# New_Project_2025-09-08_15-52-52.net
KiCad netlist of a schematic drawn in EasyEDA Pro
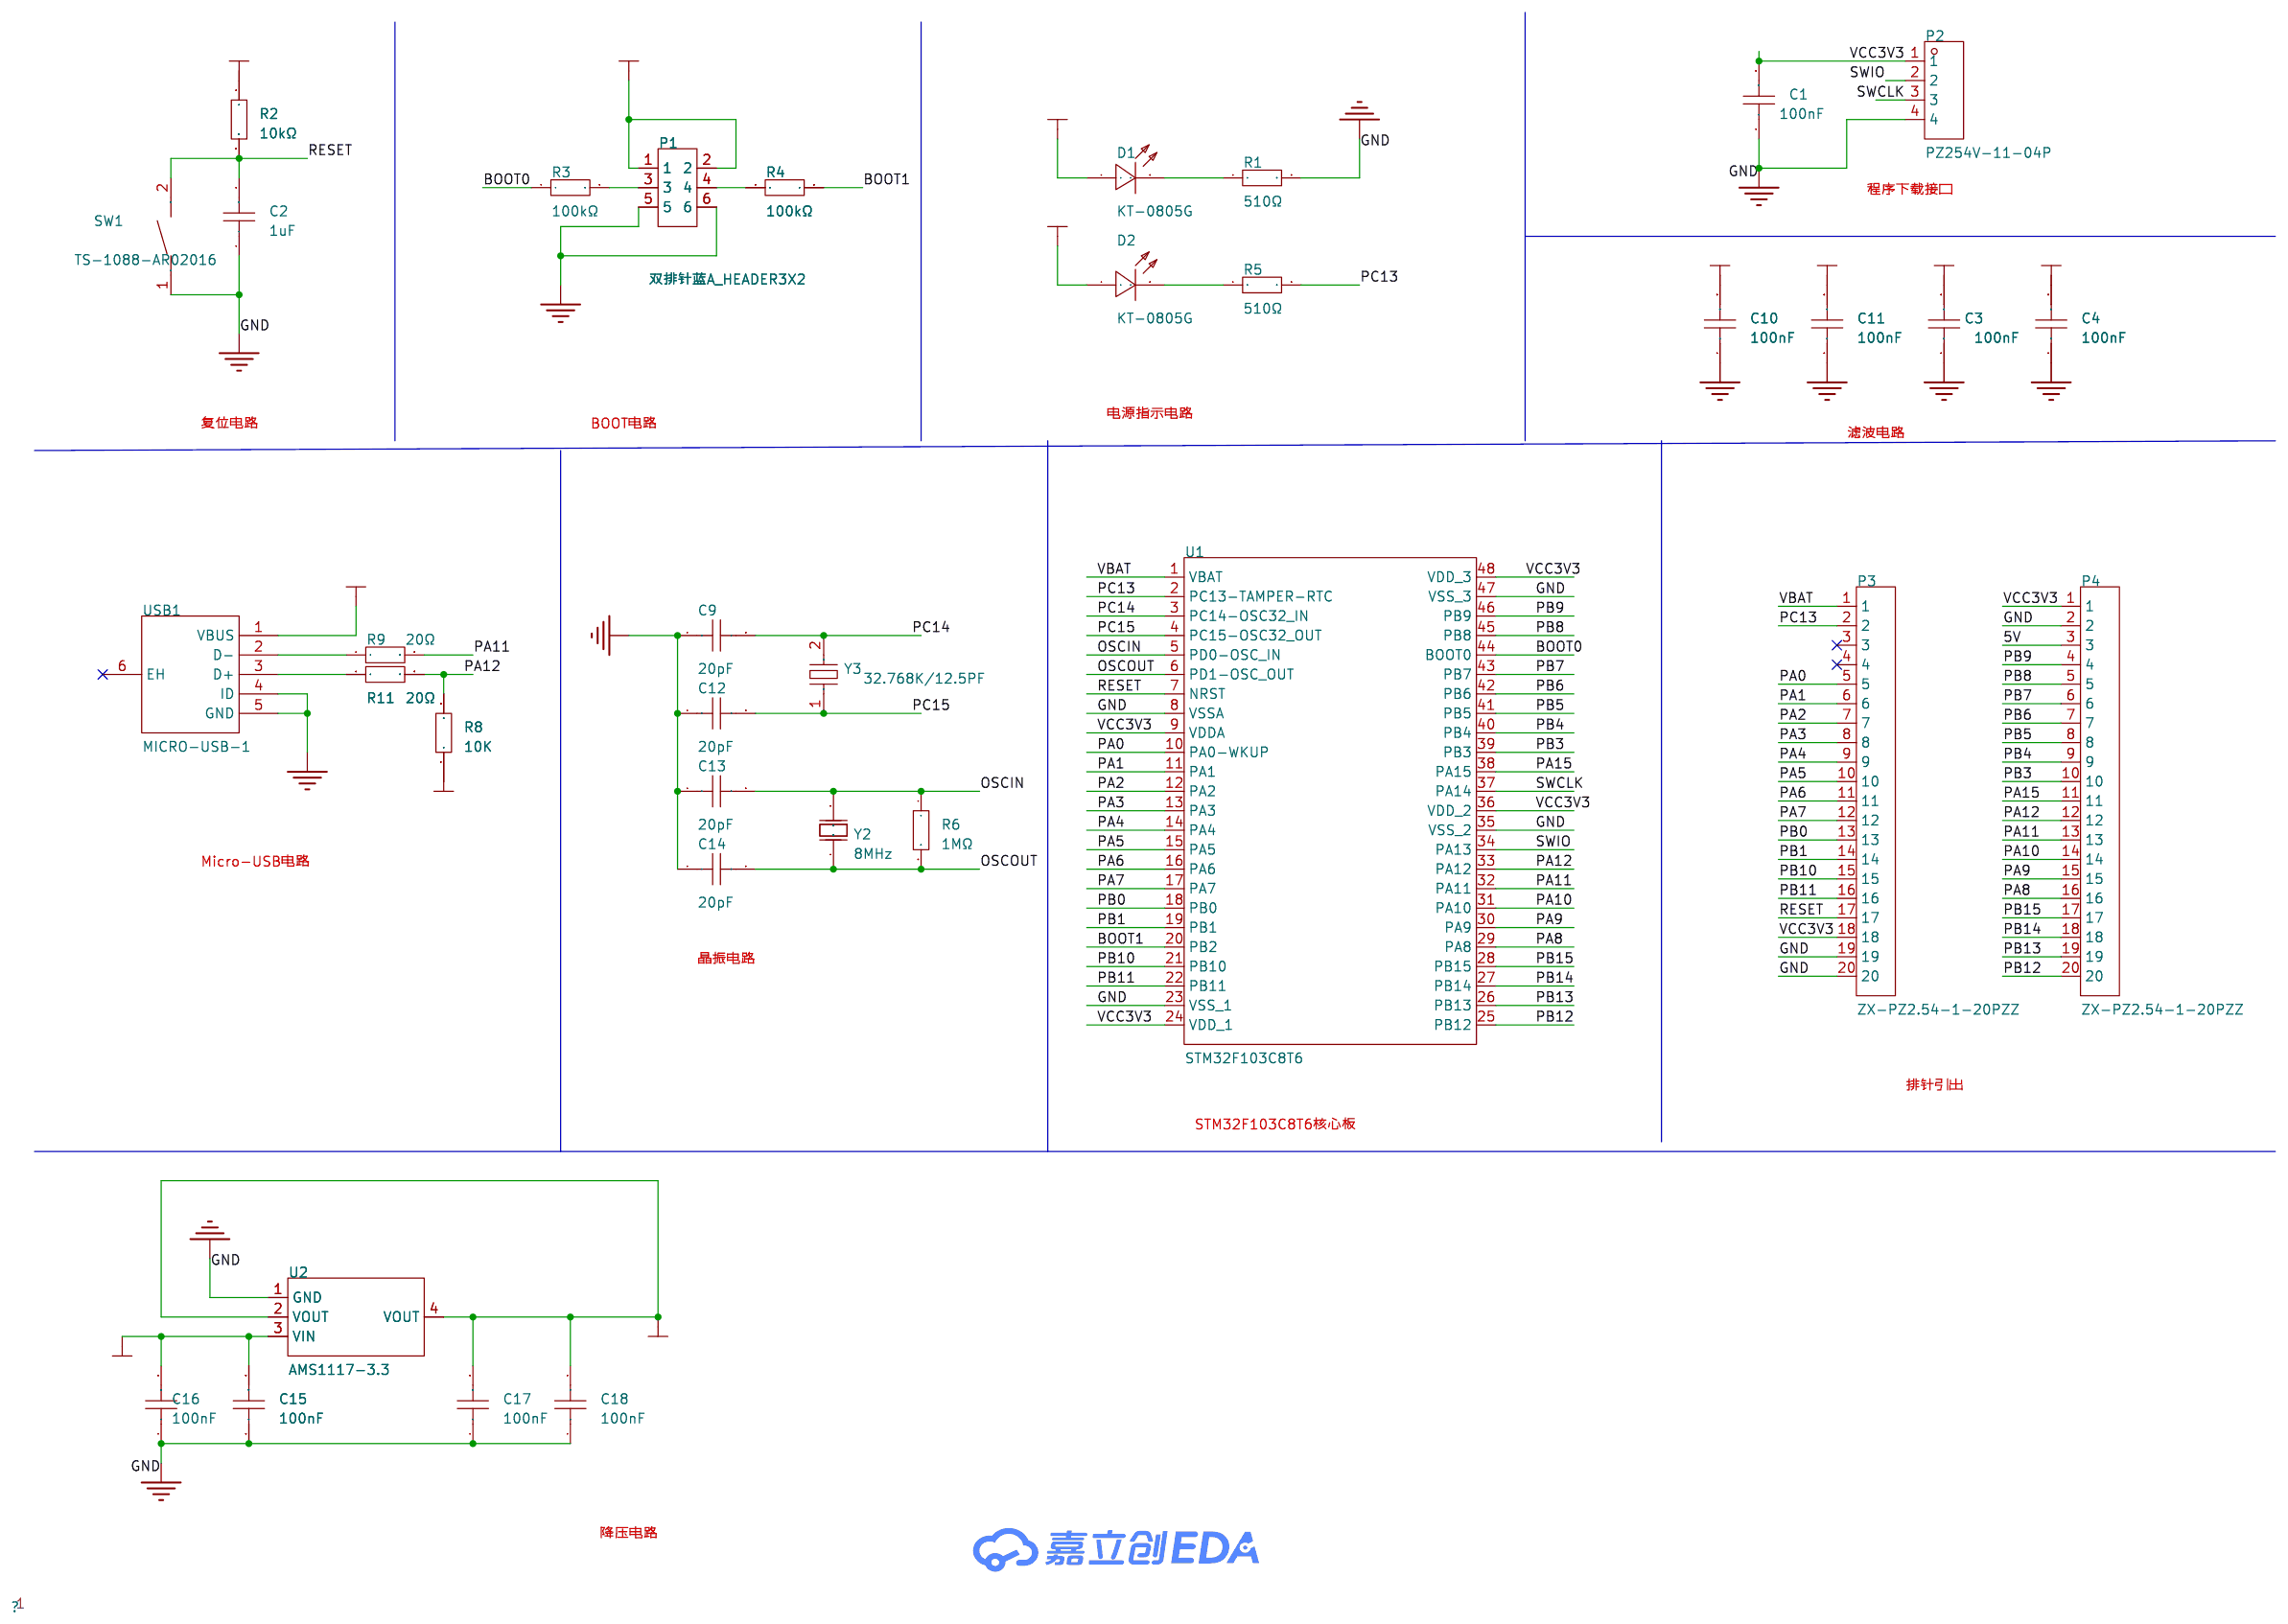
[diagram p0: schematic sheet]

(export (version "E")
  (design (tool "Eeschema 10.0.6"))
  (components
    (comp (ref "C1")
      (value "100nF")
      (footprint "easyedapro:C0603")
      (libsource (lib "easyedapro") (part "Capacitance"))
    )
    (comp (ref "C2")
      (value "1uF")
      (footprint "easyedapro:C0603")
      (libsource (lib "easyedapro") (part "Capacitance"))
    )
    (comp (ref "C3")
      (value "100nF")
      (footprint "easyedapro:C0603")
      (libsource (lib "easyedapro") (part "Capacitance"))
    )
    (comp (ref "C4")
      (value "100nF")
      (footprint "easyedapro:C0603")
      (libsource (lib "easyedapro") (part "Capacitance"))
    )
    (comp (ref "C9")
      (value "20pF")
      (footprint "easyedapro:C0603")
      (libsource (lib "easyedapro") (part "Capacitance"))
    )
    (comp (ref "C10")
      (value "100nF")
      (footprint "easyedapro:C0603")
      (libsource (lib "easyedapro") (part "Capacitance"))
    )
    (comp (ref "C11")
      (value "100nF")
      (footprint "easyedapro:C0603")
      (libsource (lib "easyedapro") (part "Capacitance"))
    )
    (comp (ref "C12")
      (value "20pF")
      (footprint "easyedapro:C0603")
      (libsource (lib "easyedapro") (part "Capacitance"))
    )
    (comp (ref "C13")
      (value "20pF")
      (footprint "easyedapro:C0603")
      (libsource (lib "easyedapro") (part "Capacitance"))
    )
    (comp (ref "C14")
      (value "20pF")
      (footprint "easyedapro:C0603")
      (libsource (lib "easyedapro") (part "Capacitance"))
    )
    (comp (ref "C15")
      (value "100nF")
      (footprint "easyedapro:C0603")
      (libsource (lib "easyedapro") (part "Capacitance"))
    )
    (comp (ref "C16")
      (value "100nF")
      (footprint "easyedapro:C0603")
      (libsource (lib "easyedapro") (part "Capacitance"))
    )
    (comp (ref "C17")
      (value "100nF")
      (footprint "easyedapro:C0603")
      (libsource (lib "easyedapro") (part "Capacitance"))
    )
    (comp (ref "C18")
      (value "100nF")
      (footprint "easyedapro:C0603")
      (libsource (lib "easyedapro") (part "Capacitance"))
    )
    (comp (ref "D1")
      (value "KT-0805G")
      (footprint "easyedapro:LED0805-R-RD")
      (fields (field (name "Manufacturer") "KENTO"))
      (libsource (lib "easyedapro") (part "0805G (Green)"))
    )
    (comp (ref "D2")
      (value "KT-0805G")
      (footprint "easyedapro:LED0805-R-RD")
      (fields (field (name "Manufacturer") "KENTO"))
      (libsource (lib "easyedapro") (part "0805G (Green)"))
    )
    (comp (ref "P1")
      (value "双排针蓝A_HEADER3X2")
      (footprint "easyedapro:HDR-TH_6P-P2.54-V-M-R2-C3-S2.54-1")
      (libsource (lib "easyedapro") (part "双排针蓝A_HEADER3X2"))
    )
    (comp (ref "P2")
      (value "PZ254V-11-04P")
      (footprint "easyedapro:HDR-TH_4P-P2.54-V-M")
      (fields (field (name "Manufacturer") "XFCN(兴飞)"))
      (libsource (lib "easyedapro") (part "PZ254V-11-04P_C2691448"))
    )
    (comp (ref "P3")
      (value "ZX-PZ2.54-1-20PZZ")
      (footprint "easyedapro:HDR-TH_20P-P2.54-V-M")
      (fields (field (name "Manufacturer") "Megastar(兆星)"))
      (libsource (lib "easyedapro") (part "ZX-PZ2.54-1-20PZZ"))
    )
    (comp (ref "P4")
      (value "ZX-PZ2.54-1-20PZZ")
      (footprint "easyedapro:HDR-TH_20P-P2.54-V-M")
      (fields (field (name "Manufacturer") "Megastar(兆星)"))
      (libsource (lib "easyedapro") (part "ZX-PZ2.54-1-20PZZ"))
    )
    (comp (ref "R1") (value "510Ω") (footprint "easyedapro:R0603") (libsource (lib "easyedapro") (part "电阻")))
    (comp (ref "R2") (value "10kΩ") (footprint "easyedapro:R0603") (libsource (lib "easyedapro") (part "电阻")))
    (comp (ref "R3")
      (value "100kΩ")
      (footprint "easyedapro:R0603")
      (libsource (lib "easyedapro") (part "电阻"))
    )
    (comp (ref "R4")
      (value "100kΩ")
      (footprint "easyedapro:R0603")
      (libsource (lib "easyedapro") (part "电阻"))
    )
    (comp (ref "R5") (value "510Ω") (footprint "easyedapro:R0603") (libsource (lib "easyedapro") (part "电阻")))
    (comp (ref "R6") (value "1MΩ") (footprint "easyedapro:R0603") (libsource (lib "easyedapro") (part "电阻")))
    (comp (ref "R8") (value "10K") (footprint "easyedapro:R0603") (libsource (lib "easyedapro") (part "电阻")))
    (comp (ref "R9") (value "20Ω") (footprint "easyedapro:R0603") (libsource (lib "easyedapro") (part "电阻")))
    (comp (ref "R11") (value "20Ω") (footprint "easyedapro:R0603") (libsource (lib "easyedapro") (part "电阻")))
    (comp (ref "SW1")
      (value "TS-1088-AR02016")
      (footprint "easyedapro:SW-SMD_L3.9-W3.0-P4.45")
      (fields (field (name "Manufacturer") "XUNPU(讯普)"))
      (libsource (lib "easyedapro") (part "TS-1088-AR02016"))
    )
    (comp (ref "U1")
      (value "STM32F103C8T6")
      (footprint "easyedapro:LQFP-48_L7.0-W7.0-P0.50-LS9.0-BL")
      (description "CPU内核:ARM-M3;CPU最大主频:72MHz;应用领域:-;")
      (fields (field (name "Manufacturer") "ST(意法半导体)"))
      (libsource (lib "easyedapro") (part "STM32F103C8T6"))
    )
    (comp (ref "U2")
      (value "AMS1117-3.3")
      (footprint "easyedapro:SOT-223-3_L6.5-W3.4-P2.30-LS7.0-BR")
      (description "输出类型:固定;工作电压:16V;输出电压:3.3V;输出电流:1A;电源纹波抑制比(PSRR):72dB@(120Hz);输出极性:正极;")
      (fields (field (name "Manufacturer") "AMS"))
      (libsource (lib "easyedapro") (part "AMS1117-3.3"))
    )
    (comp (ref "USB1")
      (value "MICRO-USB-1")
      (footprint "easyedapro:MICRO-USB-SMD_C9900008946")
      (libsource (lib "easyedapro") (part "MICRO-USB-1"))
    )
    (comp (ref "Y2")
      (value "8MHz")
      (footprint "easyedapro:HC-49U_L10.9-W4.5-P4.88")
      (description "频率:8MHz;常温频差:±30ppm;外接负载电容:-;频率稳定度(全温):±50ppm;")
      (fields (field (name "Manufacturer Part") "ATS080SM-1") (field (name "Manufacturer") "CTS(西迪斯)"))
      (libsource (lib "easyedapro") (part "ATS080SM-1"))
    )
    (comp (ref "Y3")
      (value "32.768K/12.5PF")
      (footprint "easyedapro:CRYSTAL-SMD_L3.2-W1.5-1")
      (libsource (lib "easyedapro") (part "32.768K/12.5PF"))
    )
  )
  (nets
    (net (code "1") (name "/BOOT0") (class "Default")
      (node (ref "R3") (pin "1") (pinfunction "1_1") (pintype "input"))
      (node (ref "U1") (pin "44") (pinfunction "BOOT0_44") (pintype "unspecified"))
    )
    (net (code "2") (name "/BOOT1") (class "Default")
      (node (ref "R4") (pin "2") (pinfunction "2_2") (pintype "input"))
      (node (ref "U1") (pin "20") (pinfunction "PB2_20") (pintype "unspecified"))
    )
    (net (code "3") (name "/OSCIN") (class "Default")
      (node (ref "C13") (pin "2") (pinfunction "2_2") (pintype "input"))
      (node (ref "R6") (pin "1") (pinfunction "1_1") (pintype "input"))
      (node (ref "U1") (pin "5") (pinfunction "PD0-OSC_IN_5") (pintype "unspecified"))
      (node (ref "Y2") (pin "2") (pinfunction "OSC2_2") (pintype "input"))
    )
    (net (code "4") (name "/OSCOUT") (class "Default")
      (node (ref "C14") (pin "2") (pinfunction "2_2") (pintype "input"))
      (node (ref "R6") (pin "2") (pinfunction "2_2") (pintype "input"))
      (node (ref "U1") (pin "6") (pinfunction "PD1-OSC_OUT_6") (pintype "unspecified"))
      (node (ref "Y2") (pin "1") (pinfunction "OSC1_1") (pintype "input"))
    )
    (net (code "5") (name "/PA0") (class "Default")
      (node (ref "P3") (pin "5") (pinfunction "5_5") (pintype "unspecified"))
      (node (ref "U1") (pin "10") (pinfunction "PA0-WKUP_10") (pintype "unspecified"))
    )
    (net (code "6") (name "/PA1") (class "Default")
      (node (ref "P3") (pin "6") (pinfunction "6_6") (pintype "unspecified"))
      (node (ref "U1") (pin "11") (pinfunction "PA1_11") (pintype "unspecified"))
    )
    (net (code "7") (name "/PA2") (class "Default")
      (node (ref "P3") (pin "7") (pinfunction "7_7") (pintype "unspecified"))
      (node (ref "U1") (pin "12") (pinfunction "PA2_12") (pintype "unspecified"))
    )
    (net (code "8") (name "/PA3") (class "Default")
      (node (ref "P3") (pin "8") (pinfunction "8_8") (pintype "unspecified"))
      (node (ref "U1") (pin "13") (pinfunction "PA3_13") (pintype "unspecified"))
    )
    (net (code "9") (name "/PA4") (class "Default")
      (node (ref "P3") (pin "9") (pinfunction "9_9") (pintype "unspecified"))
      (node (ref "U1") (pin "14") (pinfunction "PA4_14") (pintype "unspecified"))
    )
    (net (code "10") (name "/PA5") (class "Default")
      (node (ref "P3") (pin "10") (pinfunction "10_10") (pintype "unspecified"))
      (node (ref "U1") (pin "15") (pinfunction "PA5_15") (pintype "unspecified"))
    )
    (net (code "11") (name "/PA6") (class "Default")
      (node (ref "P3") (pin "11") (pinfunction "11_11") (pintype "unspecified"))
      (node (ref "U1") (pin "16") (pinfunction "PA6_16") (pintype "unspecified"))
    )
    (net (code "12") (name "/PA7") (class "Default")
      (node (ref "P3") (pin "12") (pinfunction "12_12") (pintype "unspecified"))
      (node (ref "U1") (pin "17") (pinfunction "PA7_17") (pintype "unspecified"))
    )
    (net (code "13") (name "/PA8") (class "Default")
      (node (ref "P4") (pin "16") (pinfunction "16_16") (pintype "unspecified"))
      (node (ref "U1") (pin "29") (pinfunction "PA8_29") (pintype "unspecified"))
    )
    (net (code "14") (name "/PA9") (class "Default")
      (node (ref "P4") (pin "15") (pinfunction "15_15") (pintype "unspecified"))
      (node (ref "U1") (pin "30") (pinfunction "PA9_30") (pintype "unspecified"))
    )
    (net (code "15") (name "/PA10") (class "Default")
      (node (ref "P4") (pin "14") (pinfunction "14_14") (pintype "unspecified"))
      (node (ref "U1") (pin "31") (pinfunction "PA10_31") (pintype "unspecified"))
    )
    (net (code "16") (name "/PA11") (class "Default")
      (node (ref "P4") (pin "13") (pinfunction "13_13") (pintype "unspecified"))
      (node (ref "R9") (pin "2") (pinfunction "2_2") (pintype "input"))
      (node (ref "U1") (pin "32") (pinfunction "PA11_32") (pintype "unspecified"))
    )
    (net (code "17") (name "/PA12") (class "Default")
      (node (ref "P4") (pin "12") (pinfunction "12_12") (pintype "unspecified"))
      (node (ref "R11") (pin "2") (pinfunction "2_2") (pintype "input"))
      (node (ref "R8") (pin "2") (pinfunction "2_2") (pintype "input"))
      (node (ref "U1") (pin "33") (pinfunction "PA12_33") (pintype "unspecified"))
    )
    (net (code "18") (name "/PA15") (class "Default")
      (node (ref "P4") (pin "11") (pinfunction "11_11") (pintype "unspecified"))
      (node (ref "U1") (pin "38") (pinfunction "PA15_38") (pintype "unspecified"))
    )
    (net (code "19") (name "/PB0") (class "Default")
      (node (ref "P3") (pin "13") (pinfunction "13_13") (pintype "unspecified"))
      (node (ref "U1") (pin "18") (pinfunction "PB0_18") (pintype "unspecified"))
    )
    (net (code "20") (name "/PB1") (class "Default")
      (node (ref "P3") (pin "14") (pinfunction "14_14") (pintype "unspecified"))
      (node (ref "U1") (pin "19") (pinfunction "PB1_19") (pintype "unspecified"))
    )
    (net (code "21") (name "/PB3") (class "Default")
      (node (ref "P4") (pin "10") (pinfunction "10_10") (pintype "unspecified"))
      (node (ref "U1") (pin "39") (pinfunction "PB3_39") (pintype "unspecified"))
    )
    (net (code "22") (name "/PB4") (class "Default")
      (node (ref "P4") (pin "9") (pinfunction "9_9") (pintype "unspecified"))
      (node (ref "U1") (pin "40") (pinfunction "PB4_40") (pintype "unspecified"))
    )
    (net (code "23") (name "/PB5") (class "Default")
      (node (ref "P4") (pin "8") (pinfunction "8_8") (pintype "unspecified"))
      (node (ref "U1") (pin "41") (pinfunction "PB5_41") (pintype "unspecified"))
    )
    (net (code "24") (name "/PB6") (class "Default")
      (node (ref "P4") (pin "7") (pinfunction "7_7") (pintype "unspecified"))
      (node (ref "U1") (pin "42") (pinfunction "PB6_42") (pintype "unspecified"))
    )
    (net (code "25") (name "/PB7") (class "Default")
      (node (ref "P4") (pin "6") (pinfunction "6_6") (pintype "unspecified"))
      (node (ref "U1") (pin "43") (pinfunction "PB7_43") (pintype "unspecified"))
    )
    (net (code "26") (name "/PB8") (class "Default")
      (node (ref "P4") (pin "5") (pinfunction "5_5") (pintype "unspecified"))
      (node (ref "U1") (pin "45") (pinfunction "PB8_45") (pintype "unspecified"))
    )
    (net (code "27") (name "/PB9") (class "Default")
      (node (ref "P4") (pin "4") (pinfunction "4_4") (pintype "unspecified"))
      (node (ref "U1") (pin "46") (pinfunction "PB9_46") (pintype "unspecified"))
    )
    (net (code "28") (name "/PB10") (class "Default")
      (node (ref "P3") (pin "15") (pinfunction "15_15") (pintype "unspecified"))
      (node (ref "U1") (pin "21") (pinfunction "PB10_21") (pintype "unspecified"))
    )
    (net (code "29") (name "/PB11") (class "Default")
      (node (ref "P3") (pin "16") (pinfunction "16_16") (pintype "unspecified"))
      (node (ref "U1") (pin "22") (pinfunction "PB11_22") (pintype "unspecified"))
    )
    (net (code "30") (name "/PB12") (class "Default")
      (node (ref "P4") (pin "20") (pinfunction "20_20") (pintype "unspecified"))
      (node (ref "U1") (pin "25") (pinfunction "PB12_25") (pintype "unspecified"))
    )
    (net (code "31") (name "/PB13") (class "Default")
      (node (ref "P4") (pin "19") (pinfunction "19_19") (pintype "unspecified"))
      (node (ref "U1") (pin "26") (pinfunction "PB13_26") (pintype "unspecified"))
    )
    (net (code "32") (name "/PB14") (class "Default")
      (node (ref "P4") (pin "18") (pinfunction "18_18") (pintype "unspecified"))
      (node (ref "U1") (pin "27") (pinfunction "PB14_27") (pintype "unspecified"))
    )
    (net (code "33") (name "/PB15") (class "Default")
      (node (ref "P4") (pin "17") (pinfunction "17_17") (pintype "unspecified"))
      (node (ref "U1") (pin "28") (pinfunction "PB15_28") (pintype "unspecified"))
    )
    (net (code "34") (name "/PC13") (class "Default")
      (node (ref "P3") (pin "2") (pinfunction "2_2") (pintype "unspecified"))
      (node (ref "R5") (pin "2") (pinfunction "2_2") (pintype "input"))
      (node (ref "U1") (pin "2") (pinfunction "PC13-TAMPER-RTC_2") (pintype "unspecified"))
    )
    (net (code "35") (name "/PC14") (class "Default")
      (node (ref "C9") (pin "2") (pinfunction "2_2") (pintype "input"))
      (node (ref "U1") (pin "3") (pinfunction "PC14-OSC32_IN_3") (pintype "unspecified"))
      (node (ref "Y3") (pin "2") (pinfunction "2_2") (pintype "input"))
    )
    (net (code "36") (name "/PC15") (class "Default")
      (node (ref "C12") (pin "2") (pinfunction "2_2") (pintype "input"))
      (node (ref "U1") (pin "4") (pinfunction "PC15-OSC32_OUT_4") (pintype "unspecified"))
      (node (ref "Y3") (pin "1") (pinfunction "1_1") (pintype "input"))
    )
    (net (code "37") (name "/RESET") (class "Default")
      (node (ref "C2") (pin "2") (pinfunction "2_2") (pintype "input"))
      (node (ref "P3") (pin "17") (pinfunction "17_17") (pintype "unspecified"))
      (node (ref "R2") (pin "2") (pinfunction "2_2") (pintype "input"))
      (node (ref "SW1") (pin "2") (pinfunction "2_2") (pintype "unspecified"))
      (node (ref "U1") (pin "7") (pinfunction "NRST_7") (pintype "unspecified"))
    )
    (net (code "38") (name "/SWCLK") (class "Default")
      (node (ref "P2") (pin "3") (pinfunction "3_3") (pintype "unspecified"))
      (node (ref "U1") (pin "37") (pinfunction "PA14_37") (pintype "unspecified"))
    )
    (net (code "39") (name "/SWIO") (class "Default")
      (node (ref "P2") (pin "2") (pinfunction "2_2") (pintype "unspecified"))
      (node (ref "U1") (pin "34") (pinfunction "PA13_34") (pintype "unspecified"))
    )
    (net (code "40") (name "/VBAT") (class "Default")
      (node (ref "P3") (pin "1") (pinfunction "1_1") (pintype "unspecified"))
      (node (ref "U1") (pin "1") (pinfunction "VBAT_1") (pintype "unspecified"))
    )
    (net (code "41") (name "5V") (class "Default")
      (node (ref "C15") (pin "2") (pinfunction "2_2") (pintype "input"))
      (node (ref "C16") (pin "2") (pinfunction "2_2") (pintype "input"))
      (node (ref "P4") (pin "3") (pinfunction "3_3") (pintype "unspecified"))
      (node (ref "R8") (pin "1") (pinfunction "1_1") (pintype "input"))
      (node (ref "U2") (pin "3") (pinfunction "VIN_3") (pintype "unspecified"))
      (node (ref "USB1") (pin "1") (pinfunction "VBUS_1") (pintype "input"))
    )
    (net (code "42") (name "GND") (class "Default")
      (node (ref "C1") (pin "1") (pinfunction "1_1") (pintype "input"))
      (node (ref "C10") (pin "1") (pinfunction "1_1") (pintype "input"))
      (node (ref "C11") (pin "1") (pinfunction "1_1") (pintype "input"))
      (node (ref "C12") (pin "1") (pinfunction "1_1") (pintype "input"))
      (node (ref "C13") (pin "1") (pinfunction "1_1") (pintype "input"))
      (node (ref "C14") (pin "1") (pinfunction "1_1") (pintype "input"))
      (node (ref "C15") (pin "1") (pinfunction "1_1") (pintype "input"))
      (node (ref "C16") (pin "1") (pinfunction "1_1") (pintype "input"))
      (node (ref "C17") (pin "1") (pinfunction "1_1") (pintype "input"))
      (node (ref "C18") (pin "1") (pinfunction "1_1") (pintype "input"))
      (node (ref "C2") (pin "1") (pinfunction "1_1") (pintype "input"))
      (node (ref "C3") (pin "1") (pinfunction "1_1") (pintype "input"))
      (node (ref "C4") (pin "1") (pinfunction "1_1") (pintype "input"))
      (node (ref "C9") (pin "1") (pinfunction "1_1") (pintype "input"))
      (node (ref "P1") (pin "5") (pinfunction "5_5") (pintype "unspecified"))
      (node (ref "P1") (pin "6") (pinfunction "6_6") (pintype "unspecified"))
      (node (ref "P2") (pin "4") (pinfunction "4_4") (pintype "unspecified"))
      (node (ref "P3") (pin "19") (pinfunction "19_19") (pintype "unspecified"))
      (node (ref "P3") (pin "20") (pinfunction "20_20") (pintype "unspecified"))
      (node (ref "P4") (pin "2") (pinfunction "2_2") (pintype "unspecified"))
      (node (ref "R1") (pin "2") (pinfunction "2_2") (pintype "input"))
      (node (ref "SW1") (pin "1") (pinfunction "1_1") (pintype "unspecified"))
      (node (ref "U1") (pin "23") (pinfunction "VSS_1_23") (pintype "unspecified"))
      (node (ref "U1") (pin "35") (pinfunction "VSS_2_35") (pintype "unspecified"))
      (node (ref "U1") (pin "47") (pinfunction "VSS_3_47") (pintype "unspecified"))
      (node (ref "U1") (pin "8") (pinfunction "VSSA_8") (pintype "unspecified"))
      (node (ref "U2") (pin "1") (pinfunction "GND_1") (pintype "unspecified"))
      (node (ref "USB1") (pin "4") (pinfunction "ID_4") (pintype "input"))
      (node (ref "USB1") (pin "5") (pinfunction "GND_5") (pintype "input"))
    )
    (net (code "43") (name "Net-(D1-K)") (class "Default")
      (node (ref "D1") (pin "2") (pinfunction "K_2") (pintype "unspecified"))
      (node (ref "R1") (pin "1") (pinfunction "1_1") (pintype "input"))
    )
    (net (code "44") (name "Net-(D2-K)") (class "Default")
      (node (ref "D2") (pin "2") (pinfunction "K_2") (pintype "unspecified"))
      (node (ref "R5") (pin "1") (pinfunction "1_1") (pintype "input"))
    )
    (net (code "45") (name "Net-(P1-Pad3)") (class "Default")
      (node (ref "P1") (pin "3") (pinfunction "3_3") (pintype "unspecified"))
      (node (ref "R3") (pin "2") (pinfunction "2_2") (pintype "input"))
    )
    (net (code "46") (name "Net-(P1-Pad4)") (class "Default")
      (node (ref "P1") (pin "4") (pinfunction "4_4") (pintype "unspecified"))
      (node (ref "R4") (pin "1") (pinfunction "1_1") (pintype "input"))
    )
    (net (code "47") (name "Net-(USB1-D+)") (class "Default")
      (node (ref "R11") (pin "1") (pinfunction "1_1") (pintype "input"))
      (node (ref "USB1") (pin "3") (pinfunction "D+_3") (pintype "input"))
    )
    (net (code "48") (name "Net-(USB1-D-)") (class "Default")
      (node (ref "R9") (pin "1") (pinfunction "1_1") (pintype "input"))
      (node (ref "USB1") (pin "2") (pinfunction "D-_2") (pintype "input"))
    )
    (net (code "49") (name "VCC3V3") (class "Default")
      (node (ref "C1") (pin "2") (pinfunction "2_2") (pintype "input"))
      (node (ref "C10") (pin "2") (pinfunction "2_2") (pintype "input"))
      (node (ref "C11") (pin "2") (pinfunction "2_2") (pintype "input"))
      (node (ref "C17") (pin "2") (pinfunction "2_2") (pintype "input"))
      (node (ref "C18") (pin "2") (pinfunction "2_2") (pintype "input"))
      (node (ref "C3") (pin "2") (pinfunction "2_2") (pintype "input"))
      (node (ref "C4") (pin "2") (pinfunction "2_2") (pintype "input"))
      (node (ref "D1") (pin "1") (pinfunction "A_1") (pintype "unspecified"))
      (node (ref "D2") (pin "1") (pinfunction "A_1") (pintype "unspecified"))
      (node (ref "P1") (pin "1") (pinfunction "1_1") (pintype "unspecified"))
      (node (ref "P1") (pin "2") (pinfunction "2_2") (pintype "unspecified"))
      (node (ref "P2") (pin "1") (pinfunction "1_1") (pintype "unspecified"))
      (node (ref "P3") (pin "18") (pinfunction "18_18") (pintype "unspecified"))
      (node (ref "P4") (pin "1") (pinfunction "1_1") (pintype "unspecified"))
      (node (ref "R2") (pin "1") (pinfunction "1_1") (pintype "input"))
      (node (ref "U1") (pin "24") (pinfunction "VDD_1_24") (pintype "unspecified"))
      (node (ref "U1") (pin "36") (pinfunction "VDD_2_36") (pintype "unspecified"))
      (node (ref "U1") (pin "48") (pinfunction "VDD_3_48") (pintype "unspecified"))
      (node (ref "U1") (pin "9") (pinfunction "VDDA_9") (pintype "unspecified"))
      (node (ref "U2") (pin "2") (pinfunction "VOUT_2") (pintype "unspecified"))
      (node (ref "U2") (pin "4") (pinfunction "VOUT_4") (pintype "unspecified"))
    )
    (net (code "50") (name "unconnected-(P3-Pad3)") (class "Default")
      (node (ref "P3") (pin "3") (pinfunction "3_3") (pintype "unspecified+no_connect"))
    )
    (net (code "51") (name "unconnected-(P3-Pad4)") (class "Default")
      (node (ref "P3") (pin "4") (pinfunction "4_4") (pintype "unspecified+no_connect"))
    )
    (net (code "52") (name "unconnected-(USB1-EH-Pad6)") (class "Default")
      (node (ref "USB1") (pin "6") (pinfunction "EH_6") (pintype "input+no_connect"))
    )
  )
)
